# MotorDriver.net
KiCad netlist of a schematic drawn in Altium Designer
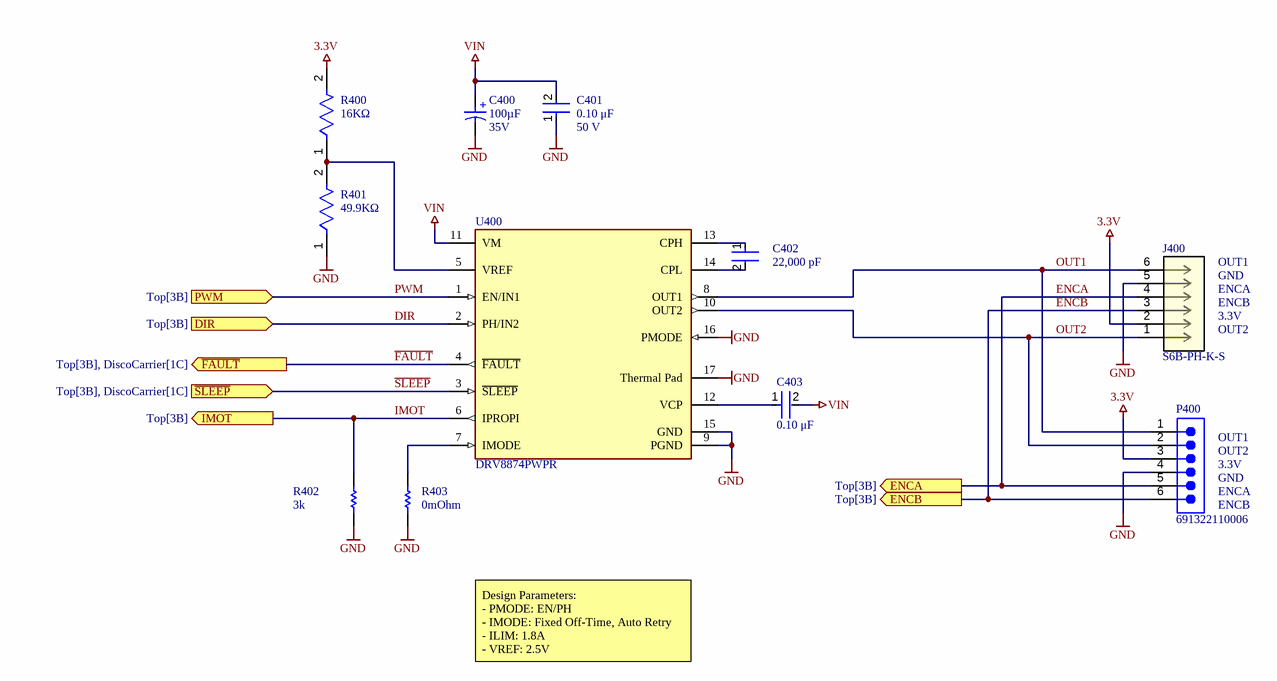
[diagram p0: MotorDriver.SchDoc]

(export (version "E")
  (design (tool "Eeschema 10.0.6"))
  (components
    (comp (ref "C400")
      (value "865080545012")
      (footprint "WCAP-ASLI_D6.3H7.7")
      (description "865080545012 Cap Aluminum Lytic 100uF 35V 20% (6.3 X 7.7mm) SMD 300mA 2000h 105C T/R")
      (fields
        (field (name "VOLTAGE RATING (DC)") "35V")
        (field (name "CAPACITANCE") "100µF")
        (field (name "TOLERANCE") "20%")
      )
      (libsource (lib "Altium Content Vault") (part "Capacitor_Polarized"))
    )
    (comp (ref "C401")
      (value "0.10 μF")
      (footprint "FP-C0603C-CF-MFG")
      (description "CAP CER 0.1UF 50V 20% X7R 0603")
      (fields
        (field (name "VOLTAGE RATING") "50 V")
        (field (name "MANUFACTURER PART NUMBER") "C0603C104M5RACTU")
        (field (name "MANUFACTURER") "KEMET")
      )
      (libsource (lib "Altium Content Vault") (part "b4654b650e69147ec39a6b967a45e02"))
    )
    (comp (ref "C402")
      (value "22,000 pF")
      (footprint "FP-C0603C-CF-MFG")
      (description "CAP CER 0.022UF 50V X7R 0603")
      (fields
        (field (name "MANUFACTURER PART NUMBER") "C0603C223M5RACTU")
        (field (name "OCTOPART") "https://octopart.com/c0603c223m5ractu-kemet-18481184")
      )
      (libsource (lib "Altium Content Vault") (part "b4654b650e69147ec39a6b967a45e02"))
    )
    (comp (ref "C403")
      (value "0.10 μF")
      (footprint "FP-C0603C-CF-MFG")
      (description "CAP CER 0.1UF 50V 20% X7R 0603")
      (fields
        (field (name "MANUFACTURER PART NUMBER") "C0603C104M5RACTU")
        (field (name "MANUFACTURER") "KEMET")
      )
      (libsource (lib "Altium Content Vault") (part "b4654b650e69147ec39a6b967a45e02"))
    )
    (comp (ref "J400")
      (value "S6B-PH-K-S")
      (footprint "CONN_S6B-PH-K-S_JST")
      (description "Description")
      (fields (field (name "COPYRIGHT") "Copyright (C) 2025 Ultra Librarian. All rights reserved."))
      (libsource (lib "robby") (part "S6B-PH-K-S"))
    )
    (comp (ref "P400")
      (value "691322110006")
      (footprint "691322110006")
      (fields (field (name "VOLTAGE") "300V"))
      (libsource (lib "Altium Content Vault") (part "TBL - 1R - 06P - Male"))
    )
    (comp (ref "R400")
      (value "16KΩ")
      (footprint "FP-RT0603-MFG")
      (description "RES SMD 16K OHM 1% 1/10W 0603")
      (fields
        (field (name "OCTOPART") "https://octopart.com/rt0603fre0716kl-yageo-1480398")
        (field (name "MANUFACTURER PART NUMBER") "RT0603FRE0716KL")
      )
      (libsource (lib "Altium Content Vault") (part "1029c3af85768c4190bb7ad29bc67b5"))
    )
    (comp (ref "R401")
      (value "49.9KΩ")
      (footprint "FP-RT0603-MFG")
      (description "RES SMD 49.9K OHM 1% 1/10W 0603")
      (fields (field (name "TOLERANCE") "0.01") (field (name "MANUFACTURER PART NUMBER") "RT0603FRE0749K9L"))
      (libsource (lib "Altium Content Vault") (part "1029c3af85768c4190bb7ad29bc67b5"))
    )
    (comp (ref "R402")
      (value "RT0603FRE073KL")
      (footprint "RESC1608X55X25LL10T15")
      (fields (field (name "MANUFACTURER") "Yageo") (field (name "PARAMETER 1") "3k"))
      (libsource (lib "Altium Content Vault") (part "RES"))
    )
    (comp (ref "R403")
      (value "RC0603JR-070RL")
      (footprint "RESC1608X55X25ML10T15")
      (description "Chip Resistor, 0 Ohm, +/- 5%, 0.1 W, -55 to 155 degC, 0603 (1608 Metric), RoHS, Tape and Reel")
      (fields
        (field (name "TOLERANCE") "5%")
        (field (name "RESISTANCE") "0mOhm")
        (field (name "MANUFACTURER") "Yageo")
      )
      (libsource (lib "Altium Content Vault") (part "RES-2"))
    )
    (comp (ref "U400")
      (value "DRV8874PWPR")
      (footprint "FP-PWP0016J-MFG")
      (description "DRV8874 H-BRIDGE MOTOR DRIVER")
      (libsource (lib "Altium Content Vault") (part "a5fc859173bb0b9b9cdb17a7cc0dfbc"))
    )
  )
  (nets
    (net (code "1") (name "/DIR") (class "Default")
      (node (ref "U400") (pin "2") (pinfunction "PH/IN2_2") (pintype "input"))
    )
    (net (code "2") (name "/ENCA") (class "Default")
      (node (ref "J400") (pin "4") (pinfunction "4_4") (pintype "passive"))
      (node (ref "P400") (pin "5") (pinfunction "5_5") (pintype "passive"))
    )
    (net (code "3") (name "/ENCB") (class "Default")
      (node (ref "J400") (pin "3") (pinfunction "3_3") (pintype "passive"))
      (node (ref "P400") (pin "6") (pinfunction "6_6") (pintype "passive"))
    )
    (net (code "4") (name "/IMOT") (class "Default")
      (node (ref "R402") (pin "2") (pinfunction "2_2") (pintype "passive"))
      (node (ref "U400") (pin "6") (pinfunction "IPROPI_6") (pintype "output"))
    )
    (net (code "5") (name "/OUT1") (class "Default")
      (node (ref "J400") (pin "6") (pinfunction "6_6") (pintype "passive"))
      (node (ref "P400") (pin "1") (pinfunction "1_1") (pintype "passive"))
      (node (ref "U400") (pin "8") (pinfunction "OUT1_8") (pintype "output"))
    )
    (net (code "6") (name "/OUT2") (class "Default")
      (node (ref "J400") (pin "1") (pinfunction "1_1") (pintype "passive"))
      (node (ref "P400") (pin "2") (pinfunction "2_2") (pintype "passive"))
      (node (ref "U400") (pin "10") (pinfunction "OUT2_10") (pintype "output"))
    )
    (net (code "7") (name "/PWM") (class "Default")
      (node (ref "U400") (pin "1") (pinfunction "EN/IN1_1") (pintype "input"))
    )
    (net (code "8") (name "/~{FAULT}") (class "Default")
      (node (ref "U400") (pin "4") (pinfunction "~{FAULT}_4") (pintype "output"))
    )
    (net (code "9") (name "/~{SLEEP}") (class "Default")
      (node (ref "U400") (pin "3") (pinfunction "~{SLEEP}_3") (pintype "input"))
    )
    (net (code "10") (name "3.3V") (class "Default")
      (node (ref "J400") (pin "2") (pinfunction "2_2") (pintype "passive"))
      (node (ref "P400") (pin "3") (pinfunction "3_3") (pintype "passive"))
      (node (ref "R400") (pin "2") (pinfunction "2_2") (pintype "passive"))
    )
    (net (code "11") (name "GND") (class "Default")
      (node (ref "C400") (pin "2") (pinfunction "N_2") (pintype "passive"))
      (node (ref "C401") (pin "1") (pinfunction "1_1") (pintype "passive"))
      (node (ref "J400") (pin "5") (pinfunction "5_5") (pintype "passive"))
      (node (ref "P400") (pin "4") (pinfunction "4_4") (pintype "passive"))
      (node (ref "R401") (pin "1") (pinfunction "1_1") (pintype "passive"))
      (node (ref "R402") (pin "1") (pinfunction "1_1") (pintype "passive"))
      (node (ref "R403") (pin "1") (pinfunction "1_1") (pintype "passive"))
      (node (ref "U400") (pin "15") (pinfunction "GND_15") (pintype "power_in"))
      (node (ref "U400") (pin "16") (pinfunction "PMODE_16") (pintype "input"))
      (node (ref "U400") (pin "17") (pinfunction "Thermal_Pad_17") (pintype "power_in"))
      (node (ref "U400") (pin "9") (pinfunction "PGND_9") (pintype "power_in"))
    )
    (net (code "12") (name "Net-(U400-CPH)") (class "Default")
      (node (ref "C402") (pin "1") (pinfunction "1_1") (pintype "passive"))
      (node (ref "U400") (pin "13") (pinfunction "CPH_13") (pintype "power_in"))
    )
    (net (code "13") (name "Net-(U400-CPL)") (class "Default")
      (node (ref "C402") (pin "2") (pinfunction "2_2") (pintype "passive"))
      (node (ref "U400") (pin "14") (pinfunction "CPL_14") (pintype "power_in"))
    )
    (net (code "14") (name "Net-(U400-IMODE)") (class "Default")
      (node (ref "R403") (pin "2") (pinfunction "2_2") (pintype "passive"))
      (node (ref "U400") (pin "7") (pinfunction "IMODE_7") (pintype "input"))
    )
    (net (code "15") (name "Net-(U400-VCP)") (class "Default")
      (node (ref "C403") (pin "1") (pinfunction "1_1") (pintype "passive"))
      (node (ref "U400") (pin "12") (pinfunction "VCP_12") (pintype "power_in"))
    )
    (net (code "16") (name "Net-(U400-VREF)") (class "Default")
      (node (ref "R400") (pin "1") (pinfunction "1_1") (pintype "passive"))
      (node (ref "R401") (pin "2") (pinfunction "2_2") (pintype "passive"))
      (node (ref "U400") (pin "5") (pinfunction "VREF_5") (pintype "power_in"))
    )
    (net (code "17") (name "VIN") (class "Default")
      (node (ref "C400") (pin "1") (pinfunction "P_1") (pintype "passive"))
      (node (ref "C401") (pin "2") (pinfunction "2_2") (pintype "passive"))
      (node (ref "C403") (pin "2") (pinfunction "2_2") (pintype "passive"))
      (node (ref "U400") (pin "11") (pinfunction "VM_11") (pintype "power_in"))
    )
  )
)
